# X-ROBOT_2.net
KiCad netlist of a schematic drawn in EasyEDA Pro
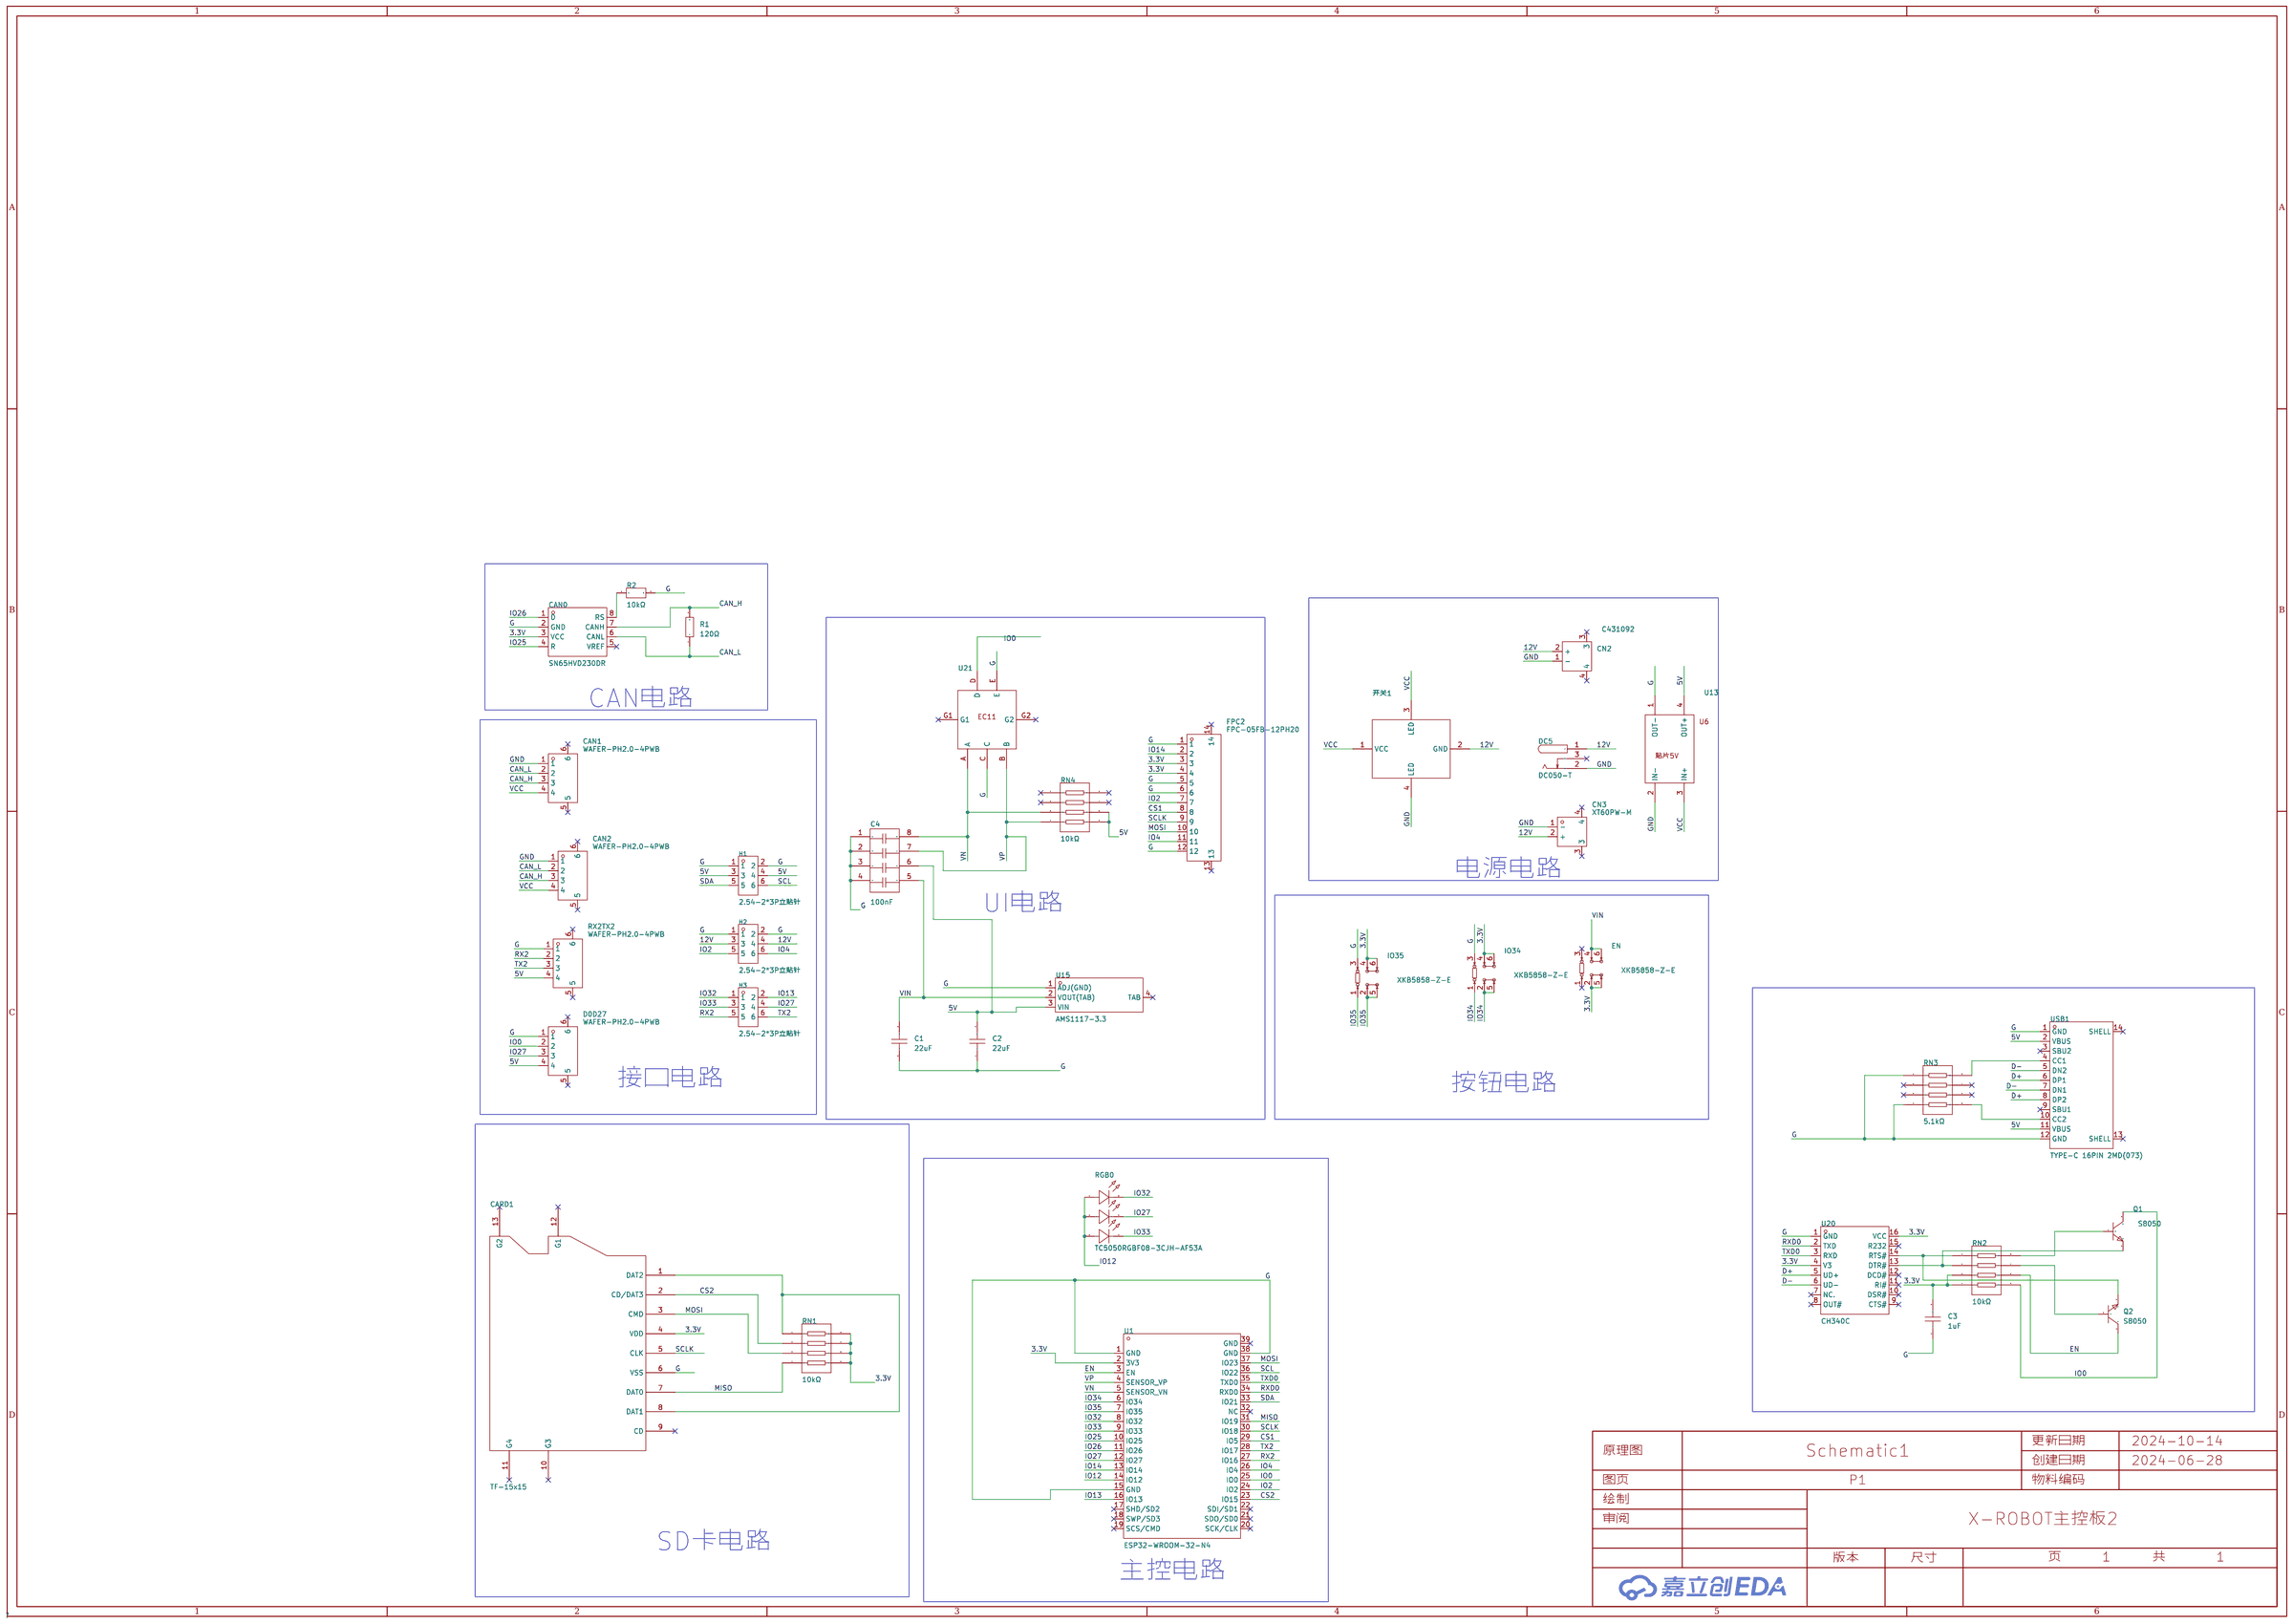
[diagram p0: schematic sheet]

(export (version "E")
  (design (tool "Eeschema 10.0.6"))
  (components
    (comp (ref "C1")
      (value "22uF")
      (footprint "easyedapro:C0805")
      (description "容值:22uF;精度:±20%;额定电压:35V;材质(温度系数):X5R;")
      (fields
        (field (name "Manufacturer Part") "CGA0805X5R226M350MT")
        (field (name "Manufacturer") "HRE(芯声)")
      )
      (libsource (lib "easyedapro") (part "CGA0805X5R226M350MT"))
    )
    (comp (ref "C2")
      (value "22uF")
      (footprint "easyedapro:C0805")
      (description "容值:22uF;精度:±20%;额定电压:35V;材质(温度系数):X5R;")
      (fields
        (field (name "Manufacturer Part") "CGA0805X5R226M350MT")
        (field (name "Manufacturer") "HRE(芯声)")
      )
      (libsource (lib "easyedapro") (part "CGA0805X5R226M350MT"))
    )
    (comp (ref "C3")
      (value "1uF")
      (footprint "easyedapro:C0603")
      (description "容值:1uF;精度:±10%;额定电压:50V;材质(温度系数):X5R;")
      (fields
        (field (name "Manufacturer Part") "CL10A105KB8NNNC")
        (field (name "Manufacturer") "SAMSUNG(三星)")
      )
      (libsource (lib "easyedapro") (part "CL10A105KB8NNNC"))
    )
    (comp (ref "C4")
      (value "100nF")
      (footprint "easyedapro:CAP-ARRAY-SMD_6124-8P-L1.6-W3.2-BL")
      (description "容值:100nF;精度:±10%;额定电压:50V;温度系数:X7R;电路形式:独立;")
      (fields (field (name "Manufacturer Part") "6124B104K500NT") (field (name "Manufacturer") "FH(风华)"))
      (libsource (lib "easyedapro") (part "6124B104K500NT"))
    )
    (comp (ref "CAN0")
      (value "SN65HVD230DR")
      (footprint "easyedapro:SOIC-8_L4.9-W3.9-P1.27-LS6.0-BL")
      (description "类型:收发器;协议类别:CAN总线;数据速率:1Mbps;")
      (fields (field (name "Manufacturer") "TI(德州仪器)"))
      (libsource (lib "easyedapro") (part "SN65HVD230DR"))
    )
    (comp (ref "CAN1")
      (value "WAFER-PH2.0-4PWB")
      (footprint "easyedapro:CONN-SMD_4P-P2.00_XUNPU_WAFER-PH2.0-4PWB")
      (description "插针结构:1x4P;间距:2mm;安装方式:卧贴;总PIN数:4P;排数:1;每排PIN数:4;额定电流:2A;工作温度范围:-25°C~+85°C;")
      (fields (field (name "Manufacturer") "XUNPU(讯普)"))
      (libsource (lib "easyedapro") (part "WAFER-PH2.0-4PWB"))
    )
    (comp (ref "CAN2")
      (value "WAFER-PH2.0-4PWB")
      (footprint "easyedapro:CONN-SMD_4P-P2.00_XUNPU_WAFER-PH2.0-4PWB")
      (description "插针结构:1x4P;间距:2mm;安装方式:卧贴;总PIN数:4P;排数:1;每排PIN数:4;额定电流:2A;工作温度范围:-25°C~+85°C;")
      (fields (field (name "Manufacturer") "XUNPU(讯普)"))
      (libsource (lib "easyedapro") (part "WAFER-PH2.0-4PWB"))
    )
    (comp (ref "CARD1")
      (value "TF-15x15")
      (footprint "easyedapro:TF-SMD_TF-15-15")
      (description "卡连接方式:自弹式;卡类型:MicroSD卡(TF卡);连接器类型:卡座;本体最大高度:-;触头材质:-;触头镀层:-;工作温度范围:-;焊接温度(最大值):-;")
      (fields (field (name "Manufacturer") "SOFNG(硕方)"))
      (libsource (lib "easyedapro") (part "TF-15×15"))
    )
    (comp (ref "CN2")
      (value "C431092")
      (footprint "easyedapro:CONN-TH_XT30PW-M")
      (description "Socket,DCsupply,XT30,male,PIN:2")
      (fields (field (name "Manufacturer Part") "XT30PW-M") (field (name "Manufacturer") "AMASS(艾迈斯)"))
      (libsource (lib "easyedapro") (part "xt30pw-m"))
    )
    (comp (ref "CN3")
      (value "XT60PW-M")
      (footprint "easyedapro:CONN-TH_XT60PW-M")
      (description "类别:-;类型1:-;")
      (fields (field (name "Manufacturer") "AMASS(艾迈斯)"))
      (libsource (lib "easyedapro") (part "XT60PW-M"))
    )
    (comp (ref "D0D27")
      (value "WAFER-PH2.0-4PWB")
      (footprint "easyedapro:CONN-SMD_4P-P2.00_XUNPU_WAFER-PH2.0-4PWB")
      (description "插针结构:1x4P;间距:2mm;安装方式:卧贴;总PIN数:4P;排数:1;每排PIN数:4;额定电流:2A;工作温度范围:-25°C~+85°C;")
      (fields (field (name "Manufacturer") "XUNPU(讯普)"))
      (libsource (lib "easyedapro") (part "WAFER-PH2.0-4PWB"))
    )
    (comp (ref "DC5")
      (value "DC050-T")
      (footprint "easyedapro:DC-IN_DC050-T")
      (description "连接器类型:DC电源插座;安装方式:卧贴;触点内径:2mm;触点外径:6.4mm;额定电流:4A;额定电压:16V;触头材质:-;触头镀层:-;工作温度范围:-;焊接温度(最大值):-;")
      (fields (field (name "Manufacturer") "SHOU HAN(首韩)"))
      (libsource (lib "easyedapro") (part "DC050-T"))
    )
    (comp (ref "EN")
      (value "XKB5858-Z-E")
      (footprint "easyedapro:SW-TH_XKB5858-Z-E")
      (description "自锁/无锁:自锁;安装方式:卧插;触点电流:100mA;额定电压 (AC):250V;额定电压 (DC):30V;带灯:不带;作用力:2.5N;机械寿命:10万次;")
      (fields (field (name "Manufacturer") "XKB Connection(中国星坤)"))
      (libsource (lib "easyedapro") (part "XKB5858-Z-E"))
    )
    (comp (ref "FPC2")
      (value "FPC-05FB-12PH20")
      (footprint "easyedapro:FPC-SMD_12P-P0.50_XUNPU_FPC-05FB-12PH20")
      (description "锁定特性:翻盖式;触点类型:双侧触点/上下接;触点数量:12P;间距:0.5mm;安装类型:卧贴;工作温度范围:-25°C~+85°C;")
      (fields (field (name "Manufacturer") "XUNPU(讯普)"))
      (libsource (lib "easyedapro") (part "FPC-05FB-12PH20"))
    )
    (comp (ref "H1")
      (value "2.54-2*3P立贴针")
      (footprint "easyedapro:HDR-SMD_6P-P2.54-V-M-R2-C5-S7.4")
      (fields (field (name "Manufacturer") "BOOMELE(博穆精密)"))
      (libsource (lib "easyedapro") (part "2.54-2*3P立贴针"))
    )
    (comp (ref "H2")
      (value "2.54-2*3P立贴针")
      (footprint "easyedapro:HDR-SMD_6P-P2.54-V-M-R2-C5-S7.4")
      (fields (field (name "Manufacturer") "BOOMELE(博穆精密)"))
      (libsource (lib "easyedapro") (part "2.54-2*3P立贴针"))
    )
    (comp (ref "H3")
      (value "2.54-2*3P立贴针")
      (footprint "easyedapro:HDR-SMD_6P-P2.54-V-M-R2-C5-S7.4")
      (fields (field (name "Manufacturer") "BOOMELE(博穆精密)"))
      (libsource (lib "easyedapro") (part "2.54-2*3P立贴针"))
    )
    (comp (ref "IO34")
      (value "XKB5858-Z-E")
      (footprint "easyedapro:SW-TH_XKB5858-Z-E")
      (description "自锁/无锁:自锁;安装方式:卧插;触点电流:100mA;额定电压 (AC):250V;额定电压 (DC):30V;带灯:不带;作用力:2.5N;机械寿命:10万次;")
      (fields (field (name "Manufacturer") "XKB Connection(中国星坤)"))
      (libsource (lib "easyedapro") (part "XKB5858-Z-E"))
    )
    (comp (ref "IO35")
      (value "XKB5858-Z-E")
      (footprint "easyedapro:SW-TH_XKB5858-Z-E")
      (description "自锁/无锁:自锁;安装方式:卧插;触点电流:100mA;额定电压 (AC):250V;额定电压 (DC):30V;带灯:不带;作用力:2.5N;机械寿命:10万次;")
      (fields (field (name "Manufacturer") "XKB Connection(中国星坤)"))
      (libsource (lib "easyedapro") (part "XKB5858-Z-E"))
    )
    (comp (ref "Q1")
      (value "S8050")
      (footprint "easyedapro:SOT-23-3_L2.9-W1.3-P1.90-LS2.3-BR")
      (description "晶体管类型:NPN;集电极电流(Ic):500mA;集射极击穿电压(Vceo):25V;功率(Pd):300mW;直流电流增益(hFE@Ic,Vce):120@50mA,1.0V;")
      (fields (field (name "Manufacturer") "宏迦橙"))
      (libsource (lib "easyedapro") (part "s8050_c20069125"))
    )
    (comp (ref "Q2")
      (value "S8050")
      (footprint "easyedapro:SOT-23-3_L2.9-W1.3-P1.90-LS2.3-BR")
      (description "晶体管类型:NPN;集电极电流(Ic):500mA;集射极击穿电压(Vceo):25V;功率(Pd):300mW;直流电流增益(hFE@Ic,Vce):120@50mA,1.0V;")
      (fields (field (name "Manufacturer") "宏迦橙"))
      (libsource (lib "easyedapro") (part "s8050_c20069125"))
    )
    (comp (ref "R1")
      (value "120Ω")
      (footprint "easyedapro:R0603")
      (description "电阻类型:厚膜电阻;阻值:120Ω;精度:±1%;功率:100mW;最大工作电压:75V;温度系数:±100ppm/°C;")
      (fields
        (field (name "Manufacturer Part") "0603WAF1200T5E")
        (field (name "Manufacturer") "UNI-ROYAL(厚声)")
      )
      (libsource (lib "easyedapro") (part "0603WAF1200T5E"))
    )
    (comp (ref "R2")
      (value "10kΩ")
      (footprint "easyedapro:R0603")
      (description "电阻类型:厚膜电阻;阻值:10kΩ;精度:±5%;功率:100mW;最大工作电压:75V;温度系数:±100ppm/°C;")
      (fields (field (name "Manufacturer Part") "FRC0603J103TS") (field (name "Manufacturer") "FOJAN(富捷)"))
      (libsource (lib "easyedapro") (part "FRC0603J103TS"))
    )
    (comp (ref "RGB0")
      (value "TC5050RGBF08-3CJH-AF53A")
      (footprint "easyedapro:LED-SMD_6P-L5.0-W5.0-TL_TC5050RGBF08")
      (description "LED贴片5050RGB灯珠高亮红绿蓝三色0.2W")
      (fields (field (name "Manufacturer") "TCWIN(天成)"))
      (libsource (lib "easyedapro") (part "TC5050RGBF08-3CJH-AF53A"))
    )
    (comp (ref "RN1")
      (value "10kΩ")
      (footprint "easyedapro:RES-ARRAY-SMD_0603-8P-L3.2-W1.6-BL")
      (description "电阻器数:4;阻值:10kΩ;精度:±5%;单个元件功率:62.5mW;温度系数:±200ppm/°C;")
      (fields
        (field (name "Manufacturer Part") "4D03WGJ0103T5E")
        (field (name "Manufacturer") "UNI-ROYAL(厚声)")
      )
      (libsource (lib "easyedapro") (part "4D03WGJ0103T5E"))
    )
    (comp (ref "RN2")
      (value "10kΩ")
      (footprint "easyedapro:RES-ARRAY-SMD_0603-8P-L3.2-W1.6-BL")
      (description "电阻器数:4;阻值:10kΩ;精度:±5%;单个元件功率:62.5mW;温度系数:±200ppm/°C;")
      (fields
        (field (name "Manufacturer Part") "4D03WGJ0103T5E")
        (field (name "Manufacturer") "UNI-ROYAL(厚声)")
      )
      (libsource (lib "easyedapro") (part "4D03WGJ0103T5E"))
    )
    (comp (ref "RN3")
      (value "5.1kΩ")
      (footprint "easyedapro:RES-ARRAY-SMD_0603-8P-L3.2-W1.6-BL")
      (description "电阻器数:4;阻值:5.1kΩ;精度:±5%;单个元件功率:62.5mW;温度系数:±200ppm/°C;")
      (fields
        (field (name "Manufacturer Part") "4D03WGJ0512T5E")
        (field (name "Manufacturer") "UNI-ROYAL(厚声)")
      )
      (libsource (lib "easyedapro") (part "4D03WGJ0512T5E"))
    )
    (comp (ref "RN4")
      (value "10kΩ")
      (footprint "easyedapro:RES-ARRAY-SMD_0603-8P-L3.2-W1.6-BL")
      (description "电阻器数:4;阻值:10kΩ;精度:±5%;单个元件功率:62.5mW;温度系数:±200ppm/°C;")
      (fields
        (field (name "Manufacturer Part") "4D03WGJ0103T5E")
        (field (name "Manufacturer") "UNI-ROYAL(厚声)")
      )
      (libsource (lib "easyedapro") (part "4D03WGJ0103T5E"))
    )
    (comp (ref "RX2TX2")
      (value "WAFER-PH2.0-4PWB")
      (footprint "easyedapro:CONN-SMD_4P-P2.00_XUNPU_WAFER-PH2.0-4PWB")
      (description "插针结构:1x4P;间距:2mm;安装方式:卧贴;总PIN数:4P;排数:1;每排PIN数:4;额定电流:2A;工作温度范围:-25°C~+85°C;")
      (fields (field (name "Manufacturer") "XUNPU(讯普)"))
      (libsource (lib "easyedapro") (part "WAFER-PH2.0-4PWB"))
    )
    (comp (ref "U1")
      (value "ESP32-WROOM-32-N4")
      (footprint "easyedapro:WIFIM-SMD_ESP32-WROOM-32-N4")
      (description "WiFi+蓝牙4.2+双核CPU,ESP32")
      (fields (field (name "Manufacturer") "ESPRESSIF(乐鑫)"))
      (libsource (lib "easyedapro") (part "ESP32-WROOM-32"))
    )
    (comp (ref "U13") (value "~") (libsource (lib "easyedapro") (part "降压模块贴片")))
    (comp (ref "U15")
      (value "AMS1117-3.3")
      (footprint "easyedapro:SOT-223-4_L6.5-W3.5-P2.30-LS7.0-BR")
      (description "输出类型:固定;最大输入电压:12V;输出电压:3.3V;最大输出电流:1A;电源纹波抑制比(PSRR):60dB@(120Hz);输出极性:正极;")
      (fields (field (name "Manufacturer") "UMW(友台半导体)"))
      (libsource (lib "easyedapro") (part "AMS1117-3.3_C347222"))
    )
    (comp (ref "U20")
      (value "CH340C")
      (footprint "easyedapro:SOP-16_L10.0-W3.9-P1.27-LS6.0-BL")
      (fields (field (name "Manufacturer") "WCH(南京沁恒)"))
      (libsource (lib "easyedapro") (part "CH340C_C7464026"))
    )
    (comp (ref "U21") (value "~") (libsource (lib "easyedapro") (part "EC11-SMT")))
    (comp (ref "USB1")
      (value "TYPE-C 16PIN 2MD(073)")
      (footprint "easyedapro:USB-C-SMD_TYPE-C-6PIN-2MD-073")
      (description "连接器类型:Type-C;标准:-;公母:母;端口数量:1;触点数量:16P;安装方式:卧贴;额定电流 - 电源:5A;工作温度范围:-25°C~+85°C;")
      (fields (field (name "Manufacturer") "SHOU HAN(首韩)"))
      (libsource (lib "easyedapro") (part "TYPE-C 16PIN 2MD(073)"))
    )
    (comp (ref "开关1") (value "~") (footprint "easyedapro:灯开关") (libsource (lib "easyedapro") (part "灯开关")))
  )
  (nets
    (net (code "1") (name "/3.3V") (class "Default")
      (node (ref "C3") (pin "2") (pinfunction "2_2") (pintype "unspecified"))
      (node (ref "CAN0") (pin "3") (pinfunction "VCC_3") (pintype "input"))
      (node (ref "CARD1") (pin "4") (pinfunction "VDD_4") (pintype "input"))
      (node (ref "EN") (pin "2") (pinfunction "2_2") (pintype "unspecified"))
      (node (ref "EN") (pin "5") (pinfunction "5_5") (pintype "unspecified"))
      (node (ref "FPC2") (pin "3") (pinfunction "3_3") (pintype "unspecified"))
      (node (ref "FPC2") (pin "4") (pinfunction "4_4") (pintype "unspecified"))
      (node (ref "IO34") (pin "4") (pinfunction "4_4") (pintype "unspecified"))
      (node (ref "IO34") (pin "6") (pinfunction "6_6") (pintype "unspecified"))
      (node (ref "IO35") (pin "4") (pinfunction "4_4") (pintype "unspecified"))
      (node (ref "IO35") (pin "6") (pinfunction "6_6") (pintype "unspecified"))
      (node (ref "RN1") (pin "5") (pinfunction "5_5") (pintype "input"))
      (node (ref "RN1") (pin "6") (pinfunction "6_6") (pintype "input"))
      (node (ref "RN1") (pin "7") (pinfunction "7_7") (pintype "input"))
      (node (ref "RN1") (pin "8") (pinfunction "8_8") (pintype "input"))
      (node (ref "RN2") (pin "3") (pinfunction "3_3") (pintype "input"))
      (node (ref "RN2") (pin "4") (pinfunction "4_4") (pintype "input"))
      (node (ref "U1") (pin "2") (pinfunction "3V3_2") (pintype "unspecified"))
      (node (ref "U20") (pin "16") (pinfunction "VCC_16") (pintype "unspecified"))
      (node (ref "U20") (pin "4") (pinfunction "V3_4") (pintype "unspecified"))
    )
    (net (code "2") (name "/5V") (class "Default")
      (node (ref "C2") (pin "2") (pinfunction "2_2") (pintype "unspecified"))
      (node (ref "C4") (pin "6") (pinfunction "6_6") (pintype "input"))
      (node (ref "D0D27") (pin "4") (pinfunction "4_4") (pintype "unspecified"))
      (node (ref "H1") (pin "3") (pinfunction "3_3") (pintype "input"))
      (node (ref "H1") (pin "4") (pinfunction "4_4") (pintype "input"))
      (node (ref "RN4") (pin "5") (pinfunction "5_5") (pintype "input"))
      (node (ref "RN4") (pin "6") (pinfunction "6_6") (pintype "input"))
      (node (ref "RX2TX2") (pin "4") (pinfunction "4_4") (pintype "unspecified"))
      (node (ref "U13") (pin "4") (pinfunction "OUT+_4") (pintype "input"))
      (node (ref "U15") (pin "3") (pinfunction "VIN_3") (pintype "unspecified"))
      (node (ref "USB1") (pin "11") (pinfunction "VBUS_11") (pintype "unspecified"))
      (node (ref "USB1") (pin "2") (pinfunction "VBUS_2") (pintype "unspecified"))
    )
    (net (code "3") (name "/12V") (class "Default")
      (node (ref "CN2") (pin "2") (pinfunction "+_2") (pintype "unspecified"))
      (node (ref "CN3") (pin "2") (pinfunction "+_2") (pintype "unspecified"))
      (node (ref "DC5") (pin "1") (pinfunction "1_1") (pintype "unspecified"))
      (node (ref "H2") (pin "3") (pinfunction "3_3") (pintype "input"))
      (node (ref "H2") (pin "4") (pinfunction "4_4") (pintype "input"))
      (node (ref "开关1") (pin "2") (pinfunction "GND_2") (pintype "input"))
    )
    (net (code "4") (name "/CAN_H") (class "Default")
      (node (ref "CAN0") (pin "7") (pinfunction "CANH_7") (pintype "input"))
      (node (ref "CAN1") (pin "3") (pinfunction "3_3") (pintype "unspecified"))
      (node (ref "CAN2") (pin "3") (pinfunction "3_3") (pintype "unspecified"))
      (node (ref "R1") (pin "2") (pinfunction "2_2") (pintype "input"))
    )
    (net (code "5") (name "/CAN_L") (class "Default")
      (node (ref "CAN0") (pin "6") (pinfunction "CANL_6") (pintype "input"))
      (node (ref "CAN1") (pin "2") (pinfunction "2_2") (pintype "unspecified"))
      (node (ref "CAN2") (pin "2") (pinfunction "2_2") (pintype "unspecified"))
      (node (ref "R1") (pin "1") (pinfunction "1_1") (pintype "input"))
    )
    (net (code "6") (name "/CS1") (class "Default")
      (node (ref "FPC2") (pin "8") (pinfunction "8_8") (pintype "unspecified"))
      (node (ref "U1") (pin "29") (pinfunction "IO5_29") (pintype "unspecified"))
    )
    (net (code "7") (name "/CS2") (class "Default")
      (node (ref "CARD1") (pin "2") (pinfunction "CD/DAT3_2") (pintype "input"))
      (node (ref "RN1") (pin "2") (pinfunction "2_2") (pintype "input"))
      (node (ref "U1") (pin "23") (pinfunction "IO15_23") (pintype "unspecified"))
    )
    (net (code "8") (name "/D+") (class "Default")
      (node (ref "U20") (pin "5") (pinfunction "UD+_5") (pintype "unspecified"))
      (node (ref "USB1") (pin "6") (pinfunction "DP1_6") (pintype "unspecified"))
      (node (ref "USB1") (pin "8") (pinfunction "DP2_8") (pintype "unspecified"))
    )
    (net (code "9") (name "/D-") (class "Default")
      (node (ref "U20") (pin "6") (pinfunction "UD-_6") (pintype "unspecified"))
      (node (ref "USB1") (pin "5") (pinfunction "DN2_5") (pintype "unspecified"))
      (node (ref "USB1") (pin "7") (pinfunction "DN1_7") (pintype "unspecified"))
    )
    (net (code "10") (name "/EN") (class "Default")
      (node (ref "Q2") (pin "3") (pinfunction "C_3") (pintype "input"))
      (node (ref "RN2") (pin "6") (pinfunction "6_6") (pintype "input"))
      (node (ref "U1") (pin "3") (pinfunction "EN_3") (pintype "unspecified"))
    )
    (net (code "11") (name "/G") (class "Default")
      (node (ref "C1") (pin "1") (pinfunction "1_1") (pintype "unspecified"))
      (node (ref "C2") (pin "1") (pinfunction "1_1") (pintype "unspecified"))
      (node (ref "C3") (pin "1") (pinfunction "1_1") (pintype "unspecified"))
      (node (ref "C4") (pin "1") (pinfunction "1_1") (pintype "input"))
      (node (ref "C4") (pin "2") (pinfunction "2_2") (pintype "input"))
      (node (ref "C4") (pin "3") (pinfunction "3_3") (pintype "input"))
      (node (ref "C4") (pin "4") (pinfunction "4_4") (pintype "input"))
      (node (ref "CAN0") (pin "2") (pinfunction "GND_2") (pintype "input"))
      (node (ref "CARD1") (pin "6") (pinfunction "VSS_6") (pintype "input"))
      (node (ref "D0D27") (pin "1") (pinfunction "1_1") (pintype "unspecified"))
      (node (ref "FPC2") (pin "1") (pinfunction "1_1") (pintype "unspecified"))
      (node (ref "FPC2") (pin "12") (pinfunction "12_12") (pintype "unspecified"))
      (node (ref "FPC2") (pin "5") (pinfunction "5_5") (pintype "unspecified"))
      (node (ref "FPC2") (pin "6") (pinfunction "6_6") (pintype "unspecified"))
      (node (ref "H1") (pin "1") (pinfunction "1_1") (pintype "input"))
      (node (ref "H1") (pin "2") (pinfunction "2_2") (pintype "input"))
      (node (ref "H2") (pin "1") (pinfunction "1_1") (pintype "input"))
      (node (ref "H2") (pin "2") (pinfunction "2_2") (pintype "input"))
      (node (ref "IO34") (pin "3") (pinfunction "3_3") (pintype "unspecified"))
      (node (ref "IO35") (pin "3") (pinfunction "3_3") (pintype "unspecified"))
      (node (ref "R2") (pin "2") (pinfunction "2_2") (pintype "unspecified"))
      (node (ref "RN3") (pin "1") (pinfunction "1_1") (pintype "input"))
      (node (ref "RN3") (pin "4") (pinfunction "4_4") (pintype "input"))
      (node (ref "RX2TX2") (pin "1") (pinfunction "1_1") (pintype "unspecified"))
      (node (ref "U1") (pin "1") (pinfunction "GND_1") (pintype "unspecified"))
      (node (ref "U1") (pin "15") (pinfunction "GND_15") (pintype "unspecified"))
      (node (ref "U1") (pin "38") (pinfunction "GND_38") (pintype "unspecified"))
      (node (ref "U13") (pin "1") (pinfunction "OUT-_1") (pintype "input"))
      (node (ref "U15") (pin "1") (pinfunction "ADJ(GND)_1") (pintype "unspecified"))
      (node (ref "U20") (pin "1") (pinfunction "GND_1") (pintype "unspecified"))
      (node (ref "U21") (pin "C") (pinfunction "C_C") (pintype "input"))
      (node (ref "U21") (pin "E") (pinfunction "E_E") (pintype "input"))
      (node (ref "USB1") (pin "1") (pinfunction "GND_1") (pintype "unspecified"))
      (node (ref "USB1") (pin "12") (pinfunction "GND_12") (pintype "unspecified"))
    )
    (net (code "12") (name "/GND") (class "Default")
      (node (ref "CAN1") (pin "1") (pinfunction "1_1") (pintype "unspecified"))
      (node (ref "CAN2") (pin "1") (pinfunction "1_1") (pintype "unspecified"))
      (node (ref "CN2") (pin "1") (pinfunction "-_1") (pintype "unspecified"))
      (node (ref "CN3") (pin "1") (pinfunction "-_1") (pintype "unspecified"))
      (node (ref "DC5") (pin "2") (pinfunction "2_2") (pintype "unspecified"))
      (node (ref "U13") (pin "2") (pinfunction "IN-_2") (pintype "input"))
      (node (ref "开关1") (pin "4") (pinfunction "LED_4") (pintype "input"))
    )
    (net (code "13") (name "/IO0") (class "Default")
      (node (ref "D0D27") (pin "2") (pinfunction "2_2") (pintype "unspecified"))
      (node (ref "Q1") (pin "3") (pinfunction "C_3") (pintype "input"))
      (node (ref "RN2") (pin "5") (pinfunction "5_5") (pintype "input"))
      (node (ref "U1") (pin "25") (pinfunction "IO0_25") (pintype "unspecified"))
      (node (ref "U21") (pin "D") (pinfunction "D_D") (pintype "input"))
    )
    (net (code "14") (name "/IO2") (class "Default")
      (node (ref "FPC2") (pin "7") (pinfunction "7_7") (pintype "unspecified"))
      (node (ref "H2") (pin "5") (pinfunction "5_5") (pintype "input"))
      (node (ref "U1") (pin "24") (pinfunction "IO2_24") (pintype "unspecified"))
    )
    (net (code "15") (name "/IO4") (class "Default")
      (node (ref "FPC2") (pin "11") (pinfunction "11_11") (pintype "unspecified"))
      (node (ref "H2") (pin "6") (pinfunction "6_6") (pintype "input"))
      (node (ref "U1") (pin "26") (pinfunction "IO4_26") (pintype "unspecified"))
    )
    (net (code "16") (name "/IO12") (class "Default")
      (node (ref "RGB0") (pin "1") (pinfunction "+_1") (pintype "unspecified"))
      (node (ref "RGB0") (pin "2") (pinfunction "+_2") (pintype "unspecified"))
      (node (ref "RGB0") (pin "3") (pinfunction "+_3") (pintype "unspecified"))
      (node (ref "U1") (pin "14") (pinfunction "IO12_14") (pintype "unspecified"))
    )
    (net (code "17") (name "/IO13") (class "Default")
      (node (ref "H3") (pin "2") (pinfunction "2_2") (pintype "input"))
      (node (ref "U1") (pin "16") (pinfunction "IO13_16") (pintype "unspecified"))
    )
    (net (code "18") (name "/IO14") (class "Default")
      (node (ref "FPC2") (pin "2") (pinfunction "2_2") (pintype "unspecified"))
      (node (ref "U1") (pin "13") (pinfunction "IO14_13") (pintype "unspecified"))
    )
    (net (code "19") (name "/IO25") (class "Default")
      (node (ref "CAN0") (pin "4") (pinfunction "R_4") (pintype "input"))
      (node (ref "U1") (pin "10") (pinfunction "IO25_10") (pintype "unspecified"))
    )
    (net (code "20") (name "/IO26") (class "Default")
      (node (ref "CAN0") (pin "1") (pinfunction "D_1") (pintype "input"))
      (node (ref "U1") (pin "11") (pinfunction "IO26_11") (pintype "unspecified"))
    )
    (net (code "21") (name "/IO27") (class "Default")
      (node (ref "D0D27") (pin "3") (pinfunction "3_3") (pintype "unspecified"))
      (node (ref "H3") (pin "4") (pinfunction "4_4") (pintype "input"))
      (node (ref "RGB0") (pin "5") (pinfunction "-_5") (pintype "unspecified"))
      (node (ref "U1") (pin "12") (pinfunction "IO27_12") (pintype "unspecified"))
    )
    (net (code "22") (name "/IO32") (class "Default")
      (node (ref "H3") (pin "1") (pinfunction "1_1") (pintype "input"))
      (node (ref "RGB0") (pin "6") (pinfunction "-_6") (pintype "unspecified"))
      (node (ref "U1") (pin "8") (pinfunction "IO32_8") (pintype "unspecified"))
    )
    (net (code "23") (name "/IO33") (class "Default")
      (node (ref "H3") (pin "3") (pinfunction "3_3") (pintype "input"))
      (node (ref "RGB0") (pin "4") (pinfunction "-_4") (pintype "unspecified"))
      (node (ref "U1") (pin "9") (pinfunction "IO33_9") (pintype "unspecified"))
    )
    (net (code "24") (name "/IO34") (class "Default")
      (node (ref "IO34") (pin "1") (pinfunction "1_1") (pintype "unspecified"))
      (node (ref "IO34") (pin "2") (pinfunction "2_2") (pintype "unspecified"))
      (node (ref "IO34") (pin "5") (pinfunction "5_5") (pintype "unspecified"))
      (node (ref "U1") (pin "6") (pinfunction "IO34_6") (pintype "unspecified"))
    )
    (net (code "25") (name "/IO35") (class "Default")
      (node (ref "IO35") (pin "1") (pinfunction "1_1") (pintype "unspecified"))
      (node (ref "IO35") (pin "2") (pinfunction "2_2") (pintype "unspecified"))
      (node (ref "IO35") (pin "5") (pinfunction "5_5") (pintype "unspecified"))
      (node (ref "U1") (pin "7") (pinfunction "IO35_7") (pintype "unspecified"))
    )
    (net (code "26") (name "/MISO") (class "Default")
      (node (ref "CARD1") (pin "7") (pinfunction "DAT0_7") (pintype "input"))
      (node (ref "RN1") (pin "4") (pinfunction "4_4") (pintype "input"))
      (node (ref "U1") (pin "31") (pinfunction "IO19_31") (pintype "unspecified"))
    )
    (net (code "27") (name "/MOSI") (class "Default")
      (node (ref "CARD1") (pin "3") (pinfunction "CMD_3") (pintype "input"))
      (node (ref "FPC2") (pin "10") (pinfunction "10_10") (pintype "unspecified"))
      (node (ref "RN1") (pin "3") (pinfunction "3_3") (pintype "input"))
      (node (ref "U1") (pin "37") (pinfunction "IO23_37") (pintype "unspecified"))
    )
    (net (code "28") (name "/RX2") (class "Default")
      (node (ref "H3") (pin "5") (pinfunction "5_5") (pintype "input"))
      (node (ref "RX2TX2") (pin "2") (pinfunction "2_2") (pintype "unspecified"))
      (node (ref "U1") (pin "27") (pinfunction "IO16_27") (pintype "unspecified"))
    )
    (net (code "29") (name "/RXD0") (class "Default")
      (node (ref "U1") (pin "34") (pinfunction "RXD0_34") (pintype "unspecified"))
      (node (ref "U20") (pin "2") (pinfunction "TXD_2") (pintype "unspecified"))
    )
    (net (code "30") (name "/SCL") (class "Default")
      (node (ref "H1") (pin "6") (pinfunction "6_6") (pintype "input"))
      (node (ref "U1") (pin "36") (pinfunction "IO22_36") (pintype "unspecified"))
    )
    (net (code "31") (name "/SCLK") (class "Default")
      (node (ref "CARD1") (pin "5") (pinfunction "CLK_5") (pintype "input"))
      (node (ref "FPC2") (pin "9") (pinfunction "9_9") (pintype "unspecified"))
      (node (ref "U1") (pin "30") (pinfunction "IO18_30") (pintype "unspecified"))
    )
    (net (code "32") (name "/SDA") (class "Default")
      (node (ref "H1") (pin "5") (pinfunction "5_5") (pintype "input"))
      (node (ref "U1") (pin "33") (pinfunction "IO21_33") (pintype "unspecified"))
    )
    (net (code "33") (name "/TX2") (class "Default")
      (node (ref "H3") (pin "6") (pinfunction "6_6") (pintype "input"))
      (node (ref "RX2TX2") (pin "3") (pinfunction "3_3") (pintype "unspecified"))
      (node (ref "U1") (pin "28") (pinfunction "IO17_28") (pintype "unspecified"))
    )
    (net (code "34") (name "/TXD0") (class "Default")
      (node (ref "U1") (pin "35") (pinfunction "TXD0_35") (pintype "unspecified"))
      (node (ref "U20") (pin "3") (pinfunction "RXD_3") (pintype "unspecified"))
    )
    (net (code "35") (name "/VCC") (class "Default")
      (node (ref "CAN1") (pin "4") (pinfunction "4_4") (pintype "unspecified"))
      (node (ref "CAN2") (pin "4") (pinfunction "4_4") (pintype "unspecified"))
      (node (ref "U13") (pin "3") (pinfunction "IN+_3") (pintype "input"))
      (node (ref "开关1") (pin "1") (pinfunction "VCC_1") (pintype "input"))
      (node (ref "开关1") (pin "3") (pinfunction "LED_3") (pintype "input"))
    )
    (net (code "36") (name "/VIN") (class "Default")
      (node (ref "C1") (pin "2") (pinfunction "2_2") (pintype "unspecified"))
      (node (ref "C4") (pin "5") (pinfunction "5_5") (pintype "input"))
      (node (ref "EN") (pin "4") (pinfunction "4_4") (pintype "unspecified"))
      (node (ref "EN") (pin "6") (pinfunction "6_6") (pintype "unspecified"))
      (node (ref "U15") (pin "2") (pinfunction "VOUT(TAB)_2") (pintype "unspecified"))
    )
    (net (code "37") (name "/VN") (class "Default")
      (node (ref "C4") (pin "8") (pinfunction "8_8") (pintype "input"))
      (node (ref "RN4") (pin "3") (pinfunction "3_3") (pintype "input"))
      (node (ref "U1") (pin "5") (pinfunction "SENSOR_VN_5") (pintype "unspecified"))
      (node (ref "U21") (pin "A") (pinfunction "A_A") (pintype "input"))
    )
    (net (code "38") (name "/VP") (class "Default")
      (node (ref "C4") (pin "7") (pinfunction "7_7") (pintype "input"))
      (node (ref "RN4") (pin "4") (pinfunction "4_4") (pintype "input"))
      (node (ref "U1") (pin "4") (pinfunction "SENSOR_VP_4") (pintype "unspecified"))
      (node (ref "U21") (pin "B") (pinfunction "B_B") (pintype "input"))
    )
    (net (code "39") (name "Net-(CAN0-RS)") (class "Default")
      (node (ref "CAN0") (pin "8") (pinfunction "RS_8") (pintype "input"))
      (node (ref "R2") (pin "1") (pinfunction "1_1") (pintype "unspecified"))
    )
    (net (code "40") (name "Net-(CARD1-DAT1)") (class "Default")
      (node (ref "CARD1") (pin "1") (pinfunction "DAT2_1") (pintype "input"))
      (node (ref "CARD1") (pin "8") (pinfunction "DAT1_8") (pintype "input"))
      (node (ref "RN1") (pin "1") (pinfunction "1_1") (pintype "input"))
    )
    (net (code "41") (name "Net-(Q1-B)") (class "Default")
      (node (ref "Q1") (pin "1") (pinfunction "B_1") (pintype "input"))
      (node (ref "RN2") (pin "8") (pinfunction "8_8") (pintype "input"))
    )
    (net (code "42") (name "Net-(Q1-E)") (class "Default")
      (node (ref "Q1") (pin "2") (pinfunction "E_2") (pintype "input"))
      (node (ref "RN2") (pin "2") (pinfunction "2_2") (pintype "input"))
      (node (ref "U20") (pin "13") (pinfunction "DTR#_13") (pintype "unspecified"))
    )
    (net (code "43") (name "Net-(Q2-B)") (class "Default")
      (node (ref "Q2") (pin "1") (pinfunction "B_1") (pintype "input"))
      (node (ref "RN2") (pin "7") (pinfunction "7_7") (pintype "input"))
    )
    (net (code "44") (name "Net-(Q2-E)") (class "Default")
      (node (ref "Q2") (pin "2") (pinfunction "E_2") (pintype "input"))
      (node (ref "RN2") (pin "1") (pinfunction "1_1") (pintype "input"))
      (node (ref "U20") (pin "14") (pinfunction "RTS#_14") (pintype "unspecified"))
    )
    (net (code "45") (name "Net-(USB1-CC1)") (class "Default")
      (node (ref "RN3") (pin "8") (pinfunction "8_8") (pintype "input"))
      (node (ref "USB1") (pin "4") (pinfunction "CC1_4") (pintype "unspecified"))
    )
    (net (code "46") (name "Net-(USB1-CC2)") (class "Default")
      (node (ref "RN3") (pin "5") (pinfunction "5_5") (pintype "input"))
      (node (ref "USB1") (pin "10") (pinfunction "CC2_10") (pintype "unspecified"))
    )
    (net (code "47") (name "unconnected-(CAN0-VREF-Pad5)") (class "Default")
      (node (ref "CAN0") (pin "5") (pinfunction "VREF_5") (pintype "input+no_connect"))
    )
    (net (code "48") (name "unconnected-(CAN1-Pad5)") (class "Default")
      (node (ref "CAN1") (pin "5") (pinfunction "5_5") (pintype "unspecified+no_connect"))
    )
    (net (code "49") (name "unconnected-(CAN1-Pad6)") (class "Default")
      (node (ref "CAN1") (pin "6") (pinfunction "6_6") (pintype "unspecified+no_connect"))
    )
    (net (code "50") (name "unconnected-(CAN2-Pad5)") (class "Default")
      (node (ref "CAN2") (pin "5") (pinfunction "5_5") (pintype "unspecified+no_connect"))
    )
    (net (code "51") (name "unconnected-(CAN2-Pad6)") (class "Default")
      (node (ref "CAN2") (pin "6") (pinfunction "6_6") (pintype "unspecified+no_connect"))
    )
    (net (code "52") (name "unconnected-(CARD1-CD-Pad9)") (class "Default")
      (node (ref "CARD1") (pin "9") (pinfunction "CD_9") (pintype "input+no_connect"))
    )
    (net (code "53") (name "unconnected-(CARD1-G1-Pad12)") (class "Default")
      (node (ref "CARD1") (pin "12") (pinfunction "G1_12") (pintype "input+no_connect"))
    )
    (net (code "54") (name "unconnected-(CARD1-G2-Pad13)") (class "Default")
      (node (ref "CARD1") (pin "13") (pinfunction "G2_13") (pintype "input+no_connect"))
    )
    (net (code "55") (name "unconnected-(CARD1-G3-Pad10)") (class "Default")
      (node (ref "CARD1") (pin "10") (pinfunction "G3_10") (pintype "input+no_connect"))
    )
    (net (code "56") (name "unconnected-(CARD1-G4-Pad11)") (class "Default")
      (node (ref "CARD1") (pin "11") (pinfunction "G4_11") (pintype "input+no_connect"))
    )
    (net (code "57") (name "unconnected-(CN2-Pad3)") (class "Default")
      (node (ref "CN2") (pin "3") (pinfunction "3_3") (pintype "unspecified+no_connect"))
    )
    (net (code "58") (name "unconnected-(CN2-Pad4)") (class "Default")
      (node (ref "CN2") (pin "4") (pinfunction "4_4") (pintype "unspecified+no_connect"))
    )
    (net (code "59") (name "unconnected-(CN3-Pad3)") (class "Default")
      (node (ref "CN3") (pin "3") (pinfunction "3_3") (pintype "unspecified+no_connect"))
    )
    (net (code "60") (name "unconnected-(CN3-Pad4)") (class "Default")
      (node (ref "CN3") (pin "4") (pinfunction "4_4") (pintype "unspecified+no_connect"))
    )
    (net (code "61") (name "unconnected-(D0D27-Pad5)") (class "Default")
      (node (ref "D0D27") (pin "5") (pinfunction "5_5") (pintype "unspecified+no_connect"))
    )
    (net (code "62") (name "unconnected-(D0D27-Pad6)") (class "Default")
      (node (ref "D0D27") (pin "6") (pinfunction "6_6") (pintype "unspecified+no_connect"))
    )
    (net (code "63") (name "unconnected-(DC5-Pad3)") (class "Default")
      (node (ref "DC5") (pin "3") (pinfunction "3_3") (pintype "unspecified+no_connect"))
    )
    (net (code "64") (name "unconnected-(EN-Pad1)") (class "Default")
      (node (ref "EN") (pin "1") (pinfunction "1_1") (pintype "unspecified+no_connect"))
    )
    (net (code "65") (name "unconnected-(EN-Pad3)") (class "Default")
      (node (ref "EN") (pin "3") (pinfunction "3_3") (pintype "unspecified+no_connect"))
    )
    (net (code "66") (name "unconnected-(FPC2-Pad13)") (class "Default")
      (node (ref "FPC2") (pin "13") (pinfunction "13_13") (pintype "unspecified+no_connect"))
    )
    (net (code "67") (name "unconnected-(FPC2-Pad14)") (class "Default")
      (node (ref "FPC2") (pin "14") (pinfunction "14_14") (pintype "unspecified+no_connect"))
    )
    (net (code "68") (name "unconnected-(RN3-Pad2)") (class "Default")
      (node (ref "RN3") (pin "2") (pinfunction "2_2") (pintype "input+no_connect"))
    )
    (net (code "69") (name "unconnected-(RN3-Pad3)") (class "Default")
      (node (ref "RN3") (pin "3") (pinfunction "3_3") (pintype "input+no_connect"))
    )
    (net (code "70") (name "unconnected-(RN3-Pad6)") (class "Default")
      (node (ref "RN3") (pin "6") (pinfunction "6_6") (pintype "input+no_connect"))
    )
    (net (code "71") (name "unconnected-(RN3-Pad7)") (class "Default")
      (node (ref "RN3") (pin "7") (pinfunction "7_7") (pintype "input+no_connect"))
    )
    (net (code "72") (name "unconnected-(RN4-Pad1)") (class "Default")
      (node (ref "RN4") (pin "1") (pinfunction "1_1") (pintype "input+no_connect"))
    )
    (net (code "73") (name "unconnected-(RN4-Pad2)") (class "Default")
      (node (ref "RN4") (pin "2") (pinfunction "2_2") (pintype "input+no_connect"))
    )
    (net (code "74") (name "unconnected-(RN4-Pad7)") (class "Default")
      (node (ref "RN4") (pin "7") (pinfunction "7_7") (pintype "input+no_connect"))
    )
    (net (code "75") (name "unconnected-(RN4-Pad8)") (class "Default")
      (node (ref "RN4") (pin "8") (pinfunction "8_8") (pintype "input+no_connect"))
    )
    (net (code "76") (name "unconnected-(RX2TX2-Pad5)") (class "Default")
      (node (ref "RX2TX2") (pin "5") (pinfunction "5_5") (pintype "unspecified+no_connect"))
    )
    (net (code "77") (name "unconnected-(RX2TX2-Pad6)") (class "Default")
      (node (ref "RX2TX2") (pin "6") (pinfunction "6_6") (pintype "unspecified+no_connect"))
    )
    (net (code "78") (name "unconnected-(U1-GND-Pad39)") (class "Default")
      (node (ref "U1") (pin "39") (pinfunction "GND_39") (pintype "unspecified+no_connect"))
    )
    (net (code "79") (name "unconnected-(U1-NC-Pad32)") (class "Default")
      (node (ref "U1") (pin "32") (pinfunction "NC_32") (pintype "unspecified+no_connect"))
    )
    (net (code "80") (name "unconnected-(U1-SCK{slash}CLK-Pad20)") (class "Default")
      (node (ref "U1") (pin "20") (pinfunction "SCK/CLK_20") (pintype "unspecified+no_connect"))
    )
    (net (code "81") (name "unconnected-(U1-SCS{slash}CMD-Pad19)") (class "Default")
      (node (ref "U1") (pin "19") (pinfunction "SCS/CMD_19") (pintype "unspecified+no_connect"))
    )
    (net (code "82") (name "unconnected-(U1-SDI{slash}SD1-Pad22)") (class "Default")
      (node (ref "U1") (pin "22") (pinfunction "SDI/SD1_22") (pintype "unspecified+no_connect"))
    )
    (net (code "83") (name "unconnected-(U1-SDO{slash}SD0-Pad21)") (class "Default")
      (node (ref "U1") (pin "21") (pinfunction "SDO/SD0_21") (pintype "unspecified+no_connect"))
    )
    (net (code "84") (name "unconnected-(U1-SHD{slash}SD2-Pad17)") (class "Default")
      (node (ref "U1") (pin "17") (pinfunction "SHD/SD2_17") (pintype "unspecified+no_connect"))
    )
    (net (code "85") (name "unconnected-(U1-SWP{slash}SD3-Pad18)") (class "Default")
      (node (ref "U1") (pin "18") (pinfunction "SWP/SD3_18") (pintype "unspecified+no_connect"))
    )
    (net (code "86") (name "unconnected-(U15-TAB-Pad4)") (class "Default")
      (node (ref "U15") (pin "4") (pinfunction "TAB_4") (pintype "unspecified+no_connect"))
    )
    (net (code "87") (name "unconnected-(U20-CTS#-Pad9)") (class "Default")
      (node (ref "U20") (pin "9") (pinfunction "CTS#_9") (pintype "unspecified+no_connect"))
    )
    (net (code "88") (name "unconnected-(U20-DCD#-Pad12)") (class "Default")
      (node (ref "U20") (pin "12") (pinfunction "DCD#_12") (pintype "unspecified+no_connect"))
    )
    (net (code "89") (name "unconnected-(U20-DSR#-Pad10)") (class "Default")
      (node (ref "U20") (pin "10") (pinfunction "DSR#_10") (pintype "unspecified+no_connect"))
    )
    (net (code "90") (name "unconnected-(U20-NC.-Pad7)") (class "Default")
      (node (ref "U20") (pin "7") (pinfunction "NC._7") (pintype "unspecified+no_connect"))
    )
    (net (code "91") (name "unconnected-(U20-OUT#-Pad8)") (class "Default")
      (node (ref "U20") (pin "8") (pinfunction "OUT#_8") (pintype "unspecified+no_connect"))
    )
    (net (code "92") (name "unconnected-(U20-R232-Pad15)") (class "Default")
      (node (ref "U20") (pin "15") (pinfunction "R232_15") (pintype "unspecified+no_connect"))
    )
    (net (code "93") (name "unconnected-(U20-RI#-Pad11)") (class "Default")
      (node (ref "U20") (pin "11") (pinfunction "RI#_11") (pintype "unspecified+no_connect"))
    )
    (net (code "94") (name "unconnected-(U21-PadG1)") (class "Default")
      (node (ref "U21") (pin "G1") (pinfunction "G1_G1") (pintype "input+no_connect"))
    )
    (net (code "95") (name "unconnected-(U21-PadG2)") (class "Default")
      (node (ref "U21") (pin "G2") (pinfunction "G2_G2") (pintype "input+no_connect"))
    )
    (net (code "96") (name "unconnected-(USB1-SBU1-Pad9)") (class "Default")
      (node (ref "USB1") (pin "9") (pinfunction "SBU1_9") (pintype "unspecified+no_connect"))
    )
    (net (code "97") (name "unconnected-(USB1-SBU2-Pad3)") (class "Default")
      (node (ref "USB1") (pin "3") (pinfunction "SBU2_3") (pintype "unspecified+no_connect"))
    )
    (net (code "98") (name "unconnected-(USB1-SHELL-Pad13)") (class "Default")
      (node (ref "USB1") (pin "13") (pinfunction "SHELL_13") (pintype "unspecified+no_connect"))
    )
    (net (code "99") (name "unconnected-(USB1-SHELL-Pad14)") (class "Default")
      (node (ref "USB1") (pin "14") (pinfunction "SHELL_14") (pintype "unspecified+no_connect"))
    )
  )
)
